# Pg1_Top_Sheet_and_Micro.net
KiCad netlist of a schematic drawn in Altium Designer
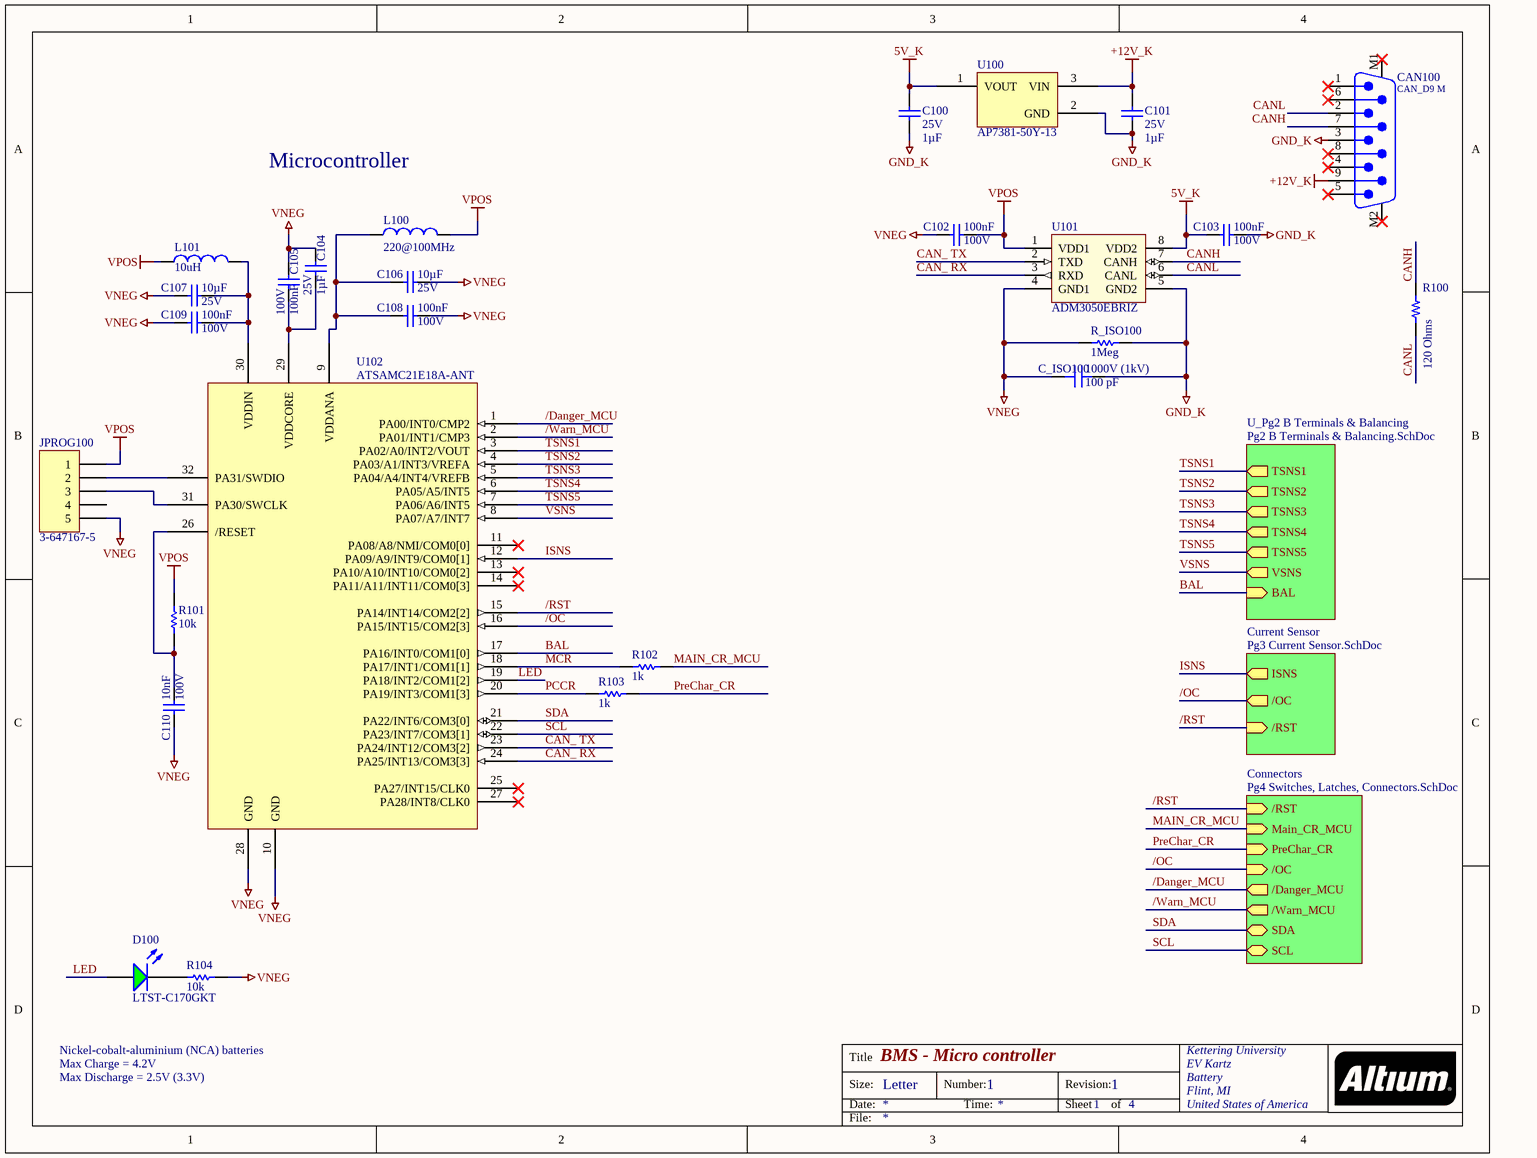
[diagram p0: Pg1 Top Sheet and Micro.SchDoc]

(export (version "E")
  (design (tool "Eeschema 10.0.6"))
  (components
    (comp (ref "C100")
      (value "1µF")
      (footprint "CAPC2012N")
      (description "Capacitor, Ceramic, 1µF, 25V, 0805, 10%, 125C")
      (fields (field (name "RATED") "25V") (field (name "Comment") "C0805C105K3RAC7210"))
      (libsource (lib "SchLib - EE391 Master") (part "C0805C105K3RAC7210"))
    )
    (comp (ref "C101")
      (value "1µF")
      (footprint "CAPC2012N")
      (description "Capacitor, Ceramic, 1µF, 25V, 0805, 10%, 125C")
      (fields (field (name "RATED") "25V") (field (name "Comment") "C0805C105K3RAC7210"))
      (libsource (lib "SchLib - EE391 Master") (part "C0805C105K3RAC7210"))
    )
    (comp (ref "C102")
      (value "100nF")
      (footprint "CAPC2012N")
      (description "Capacitor, Ceramic, 100nF, 100V, 0805, 10%, 125C")
      (fields (field (name "RATED") "100V") (field (name "Comment") "C0805C104K1RACAUTO"))
      (libsource (lib "SchLib - EE391 Master") (part "C0805C104K1RACAUTO"))
    )
    (comp (ref "C103")
      (value "100nF")
      (footprint "CAPC2012N")
      (description "Capacitor, Ceramic, 100nF, 100V, 0805, 10%, 125C")
      (fields (field (name "RATED") "100V") (field (name "Comment") "C0805C104K1RACAUTO"))
      (libsource (lib "SchLib - EE391 Master") (part "C0805C104K1RACAUTO"))
    )
    (comp (ref "C104")
      (value "1µF")
      (footprint "CAPC2012N")
      (description "Capacitor, Ceramic, 1µF, 25V, 0805, 10%, 125C")
      (fields (field (name "RATED") "25V") (field (name "Comment") "C0805C105K3RAC7210"))
      (libsource (lib "SchLib - EE391 Master") (part "C0805C105K3RAC7210"))
    )
    (comp (ref "C105")
      (value "100nF")
      (footprint "CAPC2012N")
      (description "Capacitor, Ceramic, 100nF, 100V, 0805, 10%, 125C")
      (fields (field (name "RATED") "100V") (field (name "Comment") "C0805C104K1RACAUTO"))
      (libsource (lib "SchLib - EE391 Master") (part "C0805C104K1RACAUTO"))
    )
    (comp (ref "C106")
      (value "10µF")
      (footprint "CAPC3225N")
      (description "Capacitor, Ceramic, 10µF, 25V, 0805, 10%, 125C")
      (fields (field (name "RATED") "25V") (field (name "Comment") "C1210C106K3RACAUTO"))
      (libsource (lib "SchLib - EE391 Master") (part "C1210C106K3RACAUTO"))
    )
    (comp (ref "C107")
      (value "10µF")
      (footprint "CAPC3225N")
      (description "Capacitor, Ceramic, 10µF, 25V, 0805, 10%, 125C")
      (fields (field (name "RATED") "25V") (field (name "Comment") "C1210C106K3RACAUTO"))
      (libsource (lib "SchLib - EE391 Master") (part "C1210C106K3RACAUTO"))
    )
    (comp (ref "C108")
      (value "100nF")
      (footprint "CAPC2012N")
      (description "Capacitor, Ceramic, 100nF, 100V, 0805, 10%, 125C")
      (fields (field (name "RATED") "100V") (field (name "Comment") "C0805C104K1RACAUTO"))
      (libsource (lib "SchLib - EE391 Master") (part "C0805C104K1RACAUTO"))
    )
    (comp (ref "C109")
      (value "100nF")
      (footprint "CAPC2012N")
      (description "Capacitor, Ceramic, 100nF, 100V, 0805, 10%, 125C")
      (fields (field (name "RATED") "100V") (field (name "Comment") "C0805C104K1RACAUTO"))
      (libsource (lib "SchLib - EE391 Master") (part "C0805C104K1RACAUTO"))
    )
    (comp (ref "C110")
      (value "10nF")
      (footprint "CAPC2012N")
      (description "Capacitor, Ceramic, 10nF, 100V, 0805, 10%, 125C")
      (fields (field (name "RATED") "100V") (field (name "Comment") "C0805C103K1RAC7025"))
      (libsource (lib "SchLib - EE391 Master") (part "C0805C103K1RAC7025"))
    )
    (comp (ref "CAN100")
      (value "CAN_D9 M")
      (footprint "618009211721")
      (description "Male PCB Connector without Hex Screw WR-DSUB, 8.08 mm, Angled, 9 pins")
      (fields
        (field (name "PART NUMBER") "618009211721")
        (field (name "MANUFACTURER") "Wurth Elektronik")
        (field (name "PUBLISHER") "WurthElektronik")
      )
      (libsource (lib "Altium Content Vault") (part "WE-CN-2S-2M-D9"))
    )
    (comp (ref "C_ISO100")
      (value "100 pF")
      (footprint "CAP 1206_3216 - 0.8MM")
      (description "CAP CER 100PF 1KV C0G/NP0 1206")
      (fields
        (field (name "PART NUMBER") "CL31C101JIFNFNE")
        (field (name "MANUFACTURER") "Samsung Electro-Mechanics")
        (field (name "VOLTAGE - RATED") "1000V (1kV)")
      )
      (libsource (lib "Celestial Altium Library - altium_library") (part "Capacitor"))
    )
    (comp (ref "D100")
      (value "LTST-C170GKT")
      (footprint "DIO2012N-G")
      (description "LED, SMT 0805, Green, 2.1V, 10mA")
      (libsource (lib "SchLib - EE391 Master") (part "LTST-C170GKT"))
    )
    (comp (ref "JPROG100")
      (value "3-647167-5")
      (footprint "HDR1X5 SMT")
      (description "Header, 1x5-Pin, SMT, 100mil Pitch")
      (libsource (lib "SchLib - EE391 Master") (part "Hdr 3-647167-5"))
    )
    (comp (ref "L100")
      (value "220@100MHz")
      (footprint "INDC2012N")
      (description "Inductor, 220 Ohms @ 100MHz, 2A, 50 mOhm, Ferrite Bead")
      (fields (field (name "Comment") "742792022"))
      (libsource (lib "SchLib - EE391 Master") (part "742792022"))
    )
    (comp (ref "L101")
      (value "10uH")
      (footprint "INDC3225N")
      (description "Inductor, 10uH, 700mA, 420mOhm, Ferrite Bead")
      (fields (field (name "Comment") "BRL3225T100K"))
      (libsource (lib "SchLib - EE391 Master") (part "BRL3225T100K"))
    )
    (comp (ref "R100")
      (value "120 Ohms")
      (footprint "RES 0805_2012")
      (description "RES 120 OHM 1% 1/8W 0805")
      (fields (field (name "PART NUMBER") "RC0805FR-07120RL") (field (name "MANUFACTURER") "Yageo"))
      (libsource (lib "Celestial Altium Library - altium_library") (part "Resistor"))
    )
    (comp (ref "R101")
      (value "10k")
      (footprint "RESC2012N")
      (description "Resistor, Fixed, 10 kOhm, 0805, 1%, 1/8W")
      (fields (field (name "Comment") "ERJ-6ENF1002V"))
      (libsource (lib "SchLib - EE391 Master") (part "ERJ-6ENF1002V"))
    )
    (comp (ref "R102")
      (value "1k")
      (footprint "RESC2012N")
      (description "Resistor, Fixed, 1 kOhm, 0805, 1%, 1/8W")
      (fields (field (name "Comment") "ERJ-6ENF1001V"))
      (libsource (lib "SchLib - EE391 Master") (part "ERJ-6ENF1001V"))
    )
    (comp (ref "R103")
      (value "1k")
      (footprint "RESC2012N")
      (description "Resistor, Fixed, 1 kOhm, 0805, 1%, 1/8W")
      (fields (field (name "Comment") "ERJ-6ENF1001V"))
      (libsource (lib "SchLib - EE391 Master") (part "ERJ-6ENF1001V"))
    )
    (comp (ref "R104")
      (value "10k")
      (footprint "RESC2012N")
      (description "Resistor, Fixed, 10 kOhm, 0805, 1%, 1/8W")
      (fields (field (name "Comment") "ERJ-6ENF1002V"))
      (libsource (lib "SchLib - EE391 Master") (part "ERJ-6ENF1002V"))
    )
    (comp (ref "R_ISO100")
      (value "1Meg")
      (footprint "RESC2012N")
      (description "Resistor, Fixed, 1 MOhm, 0805, 1%, 1/8W")
      (fields (field (name "Comment") "ERJ-6ENF1004V"))
      (libsource (lib "SchLib - EE391 Master") (part "ERJ-6ENF1004V"))
    )
    (comp (ref "U100")
      (value "AP7381-50Y-13")
      (footprint "DIODES INC SOT-89")
      (description "IC REG LINEAR 5V 150MA SOT89")
      (fields (field (name "MANUFACTURER") "Diodes Incorporated"))
      (libsource (lib "Celestial Altium Library - altium_library") (part "Diodes Inc AP7381"))
    )
    (comp (ref "U101")
      (value "ADM3050EBRIZ")
      (footprint "SOIC-8-300")
      (description "IC, Transceiver, CAN FD, 0.5-6V, ISOLATED")
      (libsource (lib "SchLib - EE391 Master") (part "ADM3050EBRIZ"))
    )
    (comp (ref "U102")
      (value "ATSAMC21E18A-ANT")
      (footprint "SAMC21")
      (description "ARM Microcontrollers - MCU 32TQFP,105C TEMP, GREEN, 5V, 48MHZ")
      (libsource (lib "Microcontrollers") (part "ATSAMC21E"))
    )
  )
  (nets
    (net (code "1") (name "+12V_K") (class "Default")
      (node (ref "C101") (pin "1") (pinfunction "1_1") (pintype "passive"))
      (node (ref "CAN100") (pin "9") (pinfunction "9_9") (pintype "passive"))
      (node (ref "U100") (pin "3") (pinfunction "VIN_3") (pintype "passive"))
    )
    (net (code "2") (name "/BAL") (class "Default")
      (node (ref "U102") (pin "17") (pinfunction "PA16/INT0/COM1[0]_17") (pintype "output"))
    )
    (net (code "3") (name "/CANH") (class "Default")
      (node (ref "CAN100") (pin "7") (pinfunction "7_7") (pintype "passive"))
      (node (ref "R100") (pin "2") (pinfunction "2_2") (pintype "passive"))
      (node (ref "U101") (pin "7") (pinfunction "CANH_7") (pintype "bidirectional"))
    )
    (net (code "4") (name "/CANL") (class "Default")
      (node (ref "CAN100") (pin "2") (pinfunction "2_2") (pintype "passive"))
      (node (ref "R100") (pin "1") (pinfunction "1_1") (pintype "passive"))
      (node (ref "U101") (pin "6") (pinfunction "CANL_6") (pintype "bidirectional"))
    )
    (net (code "5") (name "/CAN_ RX") (class "Default")
      (node (ref "U101") (pin "3") (pinfunction "RXD_3") (pintype "output"))
      (node (ref "U102") (pin "24") (pinfunction "PA25/INT13/COM3[3]_24") (pintype "input"))
    )
    (net (code "6") (name "/CAN_ TX") (class "Default")
      (node (ref "U101") (pin "2") (pinfunction "TXD_2") (pintype "input"))
      (node (ref "U102") (pin "23") (pinfunction "PA24/INT12/COM3[2]_23") (pintype "output"))
    )
    (net (code "7") (name "/ISNS") (class "Default")
      (node (ref "U102") (pin "12") (pinfunction "PA09/A9/INT9/COM0[1]_12") (pintype "input"))
    )
    (net (code "8") (name "/LED") (class "Default")
      (node (ref "D100") (pin "1") (pinfunction "A_1") (pintype "passive"))
      (node (ref "U102") (pin "19") (pinfunction "PA18/INT2/COM1[2]_19") (pintype "output"))
    )
    (net (code "9") (name "/MAIN_CR_MCU") (class "Default")
      (node (ref "R102") (pin "2") (pinfunction "2_2") (pintype "passive"))
    )
    (net (code "10") (name "/MCR") (class "Default")
      (node (ref "R102") (pin "1") (pinfunction "1_1") (pintype "passive"))
      (node (ref "U102") (pin "18") (pinfunction "PA17/INT1/COM1[1]_18") (pintype "output"))
    )
    (net (code "11") (name "/PCCR") (class "Default")
      (node (ref "R103") (pin "1") (pinfunction "1_1") (pintype "passive"))
      (node (ref "U102") (pin "20") (pinfunction "PA19/INT3/COM1[3]_20") (pintype "output"))
    )
    (net (code "12") (name "/PreChar_CR") (class "Default")
      (node (ref "R103") (pin "2") (pinfunction "2_2") (pintype "passive"))
    )
    (net (code "13") (name "/SCL") (class "Default")
      (node (ref "U102") (pin "22") (pinfunction "PA23/INT7/COM3[1]_22") (pintype "bidirectional"))
    )
    (net (code "14") (name "/SDA") (class "Default")
      (node (ref "U102") (pin "21") (pinfunction "PA22/INT6/COM3[0]_21") (pintype "bidirectional"))
    )
    (net (code "15") (name "/TSNS1") (class "Default")
      (node (ref "U102") (pin "3") (pinfunction "PA02/A0/INT2/VOUT_3") (pintype "input"))
    )
    (net (code "16") (name "/TSNS2") (class "Default")
      (node (ref "U102") (pin "4") (pinfunction "PA03/A1/INT3/VREFA_4") (pintype "input"))
    )
    (net (code "17") (name "/TSNS3") (class "Default")
      (node (ref "U102") (pin "5") (pinfunction "PA04/A4/INT4/VREFB_5") (pintype "input"))
    )
    (net (code "18") (name "/TSNS4") (class "Default")
      (node (ref "U102") (pin "6") (pinfunction "PA05/A5/INT5_6") (pintype "input"))
    )
    (net (code "19") (name "/TSNS5") (class "Default")
      (node (ref "U102") (pin "7") (pinfunction "PA06/A6/INT5_7") (pintype "input"))
    )
    (net (code "20") (name "/VSNS") (class "Default")
      (node (ref "U102") (pin "8") (pinfunction "PA07/A7/INT7_8") (pintype "input"))
    )
    (net (code "21") (name "/{slash}Danger_MCU") (class "Default")
      (node (ref "U102") (pin "1") (pinfunction "PA00/INT0/CMP2_1") (pintype "input"))
    )
    (net (code "22") (name "/{slash}OC") (class "Default")
      (node (ref "U102") (pin "16") (pinfunction "PA15/INT15/COM2[3]_16") (pintype "input"))
    )
    (net (code "23") (name "/{slash}RST") (class "Default")
      (node (ref "U102") (pin "15") (pinfunction "PA14/INT14/COM2[2]_15") (pintype "output"))
    )
    (net (code "24") (name "/{slash}Warn_MCU") (class "Default")
      (node (ref "U102") (pin "2") (pinfunction "PA01/INT1/CMP3_2") (pintype "input"))
    )
    (net (code "25") (name "5V_K") (class "Default")
      (node (ref "C100") (pin "1") (pinfunction "1_1") (pintype "passive"))
      (node (ref "C103") (pin "1") (pinfunction "1_1") (pintype "passive"))
      (node (ref "U100") (pin "1") (pinfunction "VOUT_1") (pintype "passive"))
      (node (ref "U101") (pin "8") (pinfunction "VDD2_8") (pintype "power_in"))
    )
    (net (code "26") (name "GND_K") (class "Default")
      (node (ref "C100") (pin "2") (pinfunction "2_2") (pintype "passive"))
      (node (ref "C101") (pin "2") (pinfunction "2_2") (pintype "passive"))
      (node (ref "C103") (pin "2") (pinfunction "2_2") (pintype "passive"))
      (node (ref "CAN100") (pin "3") (pinfunction "3_3") (pintype "passive"))
      (node (ref "C_ISO100") (pin "2") (pinfunction "2_2") (pintype "passive"))
      (node (ref "R_ISO100") (pin "2") (pinfunction "2_2") (pintype "passive"))
      (node (ref "U100") (pin "2") (pinfunction "GND_2") (pintype "passive"))
      (node (ref "U101") (pin "5") (pinfunction "GND2_5") (pintype "power_in"))
    )
    (net (code "27") (name "Net-(D100-K)") (class "Default")
      (node (ref "D100") (pin "2") (pinfunction "K_2") (pintype "passive"))
      (node (ref "R104") (pin "2") (pinfunction "2_2") (pintype "passive"))
    )
    (net (code "28") (name "Net-(U102-PA30{slash}SWCLK)") (class "Default")
      (node (ref "JPROG100") (pin "3") (pinfunction "3_3") (pintype "passive"))
      (node (ref "U102") (pin "31") (pinfunction "PA30/SWCLK_31") (pintype "passive"))
    )
    (net (code "29") (name "Net-(U102-PA31{slash}SWDIO)") (class "Default")
      (node (ref "JPROG100") (pin "2") (pinfunction "2_2") (pintype "passive"))
      (node (ref "U102") (pin "32") (pinfunction "PA31/SWDIO_32") (pintype "passive"))
    )
    (net (code "30") (name "Net-(U102-VDDANA)") (class "Default")
      (node (ref "C106") (pin "1") (pinfunction "1_1") (pintype "passive"))
      (node (ref "C108") (pin "1") (pinfunction "1_1") (pintype "passive"))
      (node (ref "L100") (pin "1") (pinfunction "1_1") (pintype "passive"))
      (node (ref "U102") (pin "9") (pinfunction "VDDANA_9") (pintype "passive"))
    )
    (net (code "31") (name "Net-(U102-VDDCORE)") (class "Default")
      (node (ref "C104") (pin "2") (pinfunction "2_2") (pintype "passive"))
      (node (ref "C105") (pin "2") (pinfunction "2_2") (pintype "passive"))
      (node (ref "U102") (pin "29") (pinfunction "VDDCORE_29") (pintype "passive"))
    )
    (net (code "32") (name "Net-(U102-VDDIN)") (class "Default")
      (node (ref "C107") (pin "2") (pinfunction "2_2") (pintype "passive"))
      (node (ref "C109") (pin "2") (pinfunction "2_2") (pintype "passive"))
      (node (ref "L101") (pin "2") (pinfunction "2_2") (pintype "passive"))
      (node (ref "U102") (pin "30") (pinfunction "VDDIN_30") (pintype "passive"))
    )
    (net (code "33") (name "Net-(U102-{slash}RESET)") (class "Default")
      (node (ref "C110") (pin "1") (pinfunction "1_1") (pintype "passive"))
      (node (ref "R101") (pin "2") (pinfunction "2_2") (pintype "passive"))
      (node (ref "U102") (pin "26") (pinfunction "/RESET_26") (pintype "passive"))
    )
    (net (code "34") (name "VNEG") (class "Default")
      (node (ref "C102") (pin "1") (pinfunction "1_1") (pintype "passive"))
      (node (ref "C104") (pin "1") (pinfunction "1_1") (pintype "passive"))
      (node (ref "C105") (pin "1") (pinfunction "1_1") (pintype "passive"))
      (node (ref "C106") (pin "2") (pinfunction "2_2") (pintype "passive"))
      (node (ref "C107") (pin "1") (pinfunction "1_1") (pintype "passive"))
      (node (ref "C108") (pin "2") (pinfunction "2_2") (pintype "passive"))
      (node (ref "C109") (pin "1") (pinfunction "1_1") (pintype "passive"))
      (node (ref "C110") (pin "2") (pinfunction "2_2") (pintype "passive"))
      (node (ref "C_ISO100") (pin "1") (pinfunction "1_1") (pintype "passive"))
      (node (ref "JPROG100") (pin "5") (pinfunction "5_5") (pintype "passive"))
      (node (ref "R104") (pin "1") (pinfunction "1_1") (pintype "passive"))
      (node (ref "R_ISO100") (pin "1") (pinfunction "1_1") (pintype "passive"))
      (node (ref "U101") (pin "4") (pinfunction "GND1_4") (pintype "power_in"))
      (node (ref "U102") (pin "10") (pinfunction "GND_10") (pintype "passive"))
      (node (ref "U102") (pin "28") (pinfunction "GND_28") (pintype "passive"))
    )
    (net (code "35") (name "VPOS") (class "Default")
      (node (ref "C102") (pin "2") (pinfunction "2_2") (pintype "passive"))
      (node (ref "JPROG100") (pin "1") (pinfunction "1_1") (pintype "passive"))
      (node (ref "L100") (pin "2") (pinfunction "2_2") (pintype "passive"))
      (node (ref "L101") (pin "1") (pinfunction "1_1") (pintype "passive"))
      (node (ref "R101") (pin "1") (pinfunction "1_1") (pintype "passive"))
      (node (ref "U101") (pin "1") (pinfunction "VDD1_1") (pintype "power_in"))
    )
    (net (code "36") (name "unconnected-(CAN100-Pad1)") (class "Default")
      (node (ref "CAN100") (pin "1") (pinfunction "1_1") (pintype "passive+no_connect"))
    )
    (net (code "37") (name "unconnected-(CAN100-Pad4)") (class "Default")
      (node (ref "CAN100") (pin "4") (pinfunction "4_4") (pintype "passive+no_connect"))
    )
    (net (code "38") (name "unconnected-(CAN100-Pad5)") (class "Default")
      (node (ref "CAN100") (pin "5") (pinfunction "5_5") (pintype "passive+no_connect"))
    )
    (net (code "39") (name "unconnected-(CAN100-Pad6)") (class "Default")
      (node (ref "CAN100") (pin "6") (pinfunction "6_6") (pintype "passive+no_connect"))
    )
    (net (code "40") (name "unconnected-(CAN100-Pad8)") (class "Default")
      (node (ref "CAN100") (pin "8") (pinfunction "8_8") (pintype "passive+no_connect"))
    )
    (net (code "41") (name "unconnected-(CAN100-PadM1)") (class "Default")
      (node (ref "CAN100") (pin "M1") (pinfunction "M1_M1") (pintype "passive+no_connect"))
    )
    (net (code "42") (name "unconnected-(CAN100-PadM2)") (class "Default")
      (node (ref "CAN100") (pin "M2") (pinfunction "M2_M2") (pintype "passive+no_connect"))
    )
    (net (code "43") (name "unconnected-(JPROG100-Pad4)") (class "Default")
      (node (ref "JPROG100") (pin "4") (pinfunction "4_4") (pintype "passive"))
    )
    (net (code "44") (name "unconnected-(U102-PA08{slash}A8{slash}NMI{slash}COM0[0]-Pad11)") (class "Default")
      (node (ref "U102") (pin "11") (pinfunction "PA08/A8/NMI/COM0[0]_11") (pintype "passive+no_connect"))
    )
    (net (code "45") (name "unconnected-(U102-PA10{slash}A10{slash}INT10{slash}COM0[2]-Pad13)") (class "Default")
      (node (ref "U102") (pin "13") (pinfunction "PA10/A10/INT10/COM0[2]_13") (pintype "passive+no_connect"))
    )
    (net (code "46") (name "unconnected-(U102-PA11{slash}A11{slash}INT11{slash}COM0[3]-Pad14)") (class "Default")
      (node (ref "U102") (pin "14") (pinfunction "PA11/A11/INT11/COM0[3]_14") (pintype "passive+no_connect"))
    )
    (net (code "47") (name "unconnected-(U102-PA27{slash}INT15{slash}CLK0-Pad25)") (class "Default")
      (node (ref "U102") (pin "25") (pinfunction "PA27/INT15/CLK0_25") (pintype "passive+no_connect"))
    )
    (net (code "48") (name "unconnected-(U102-PA28{slash}INT8{slash}CLK0-Pad27)") (class "Default")
      (node (ref "U102") (pin "27") (pinfunction "PA28/INT8/CLK0_27") (pintype "passive+no_connect"))
    )
  )
)
